# SCH_PIANO_PIC16F88_2024-05-19.net
KiCad netlist of a schematic drawn in EasyEDA
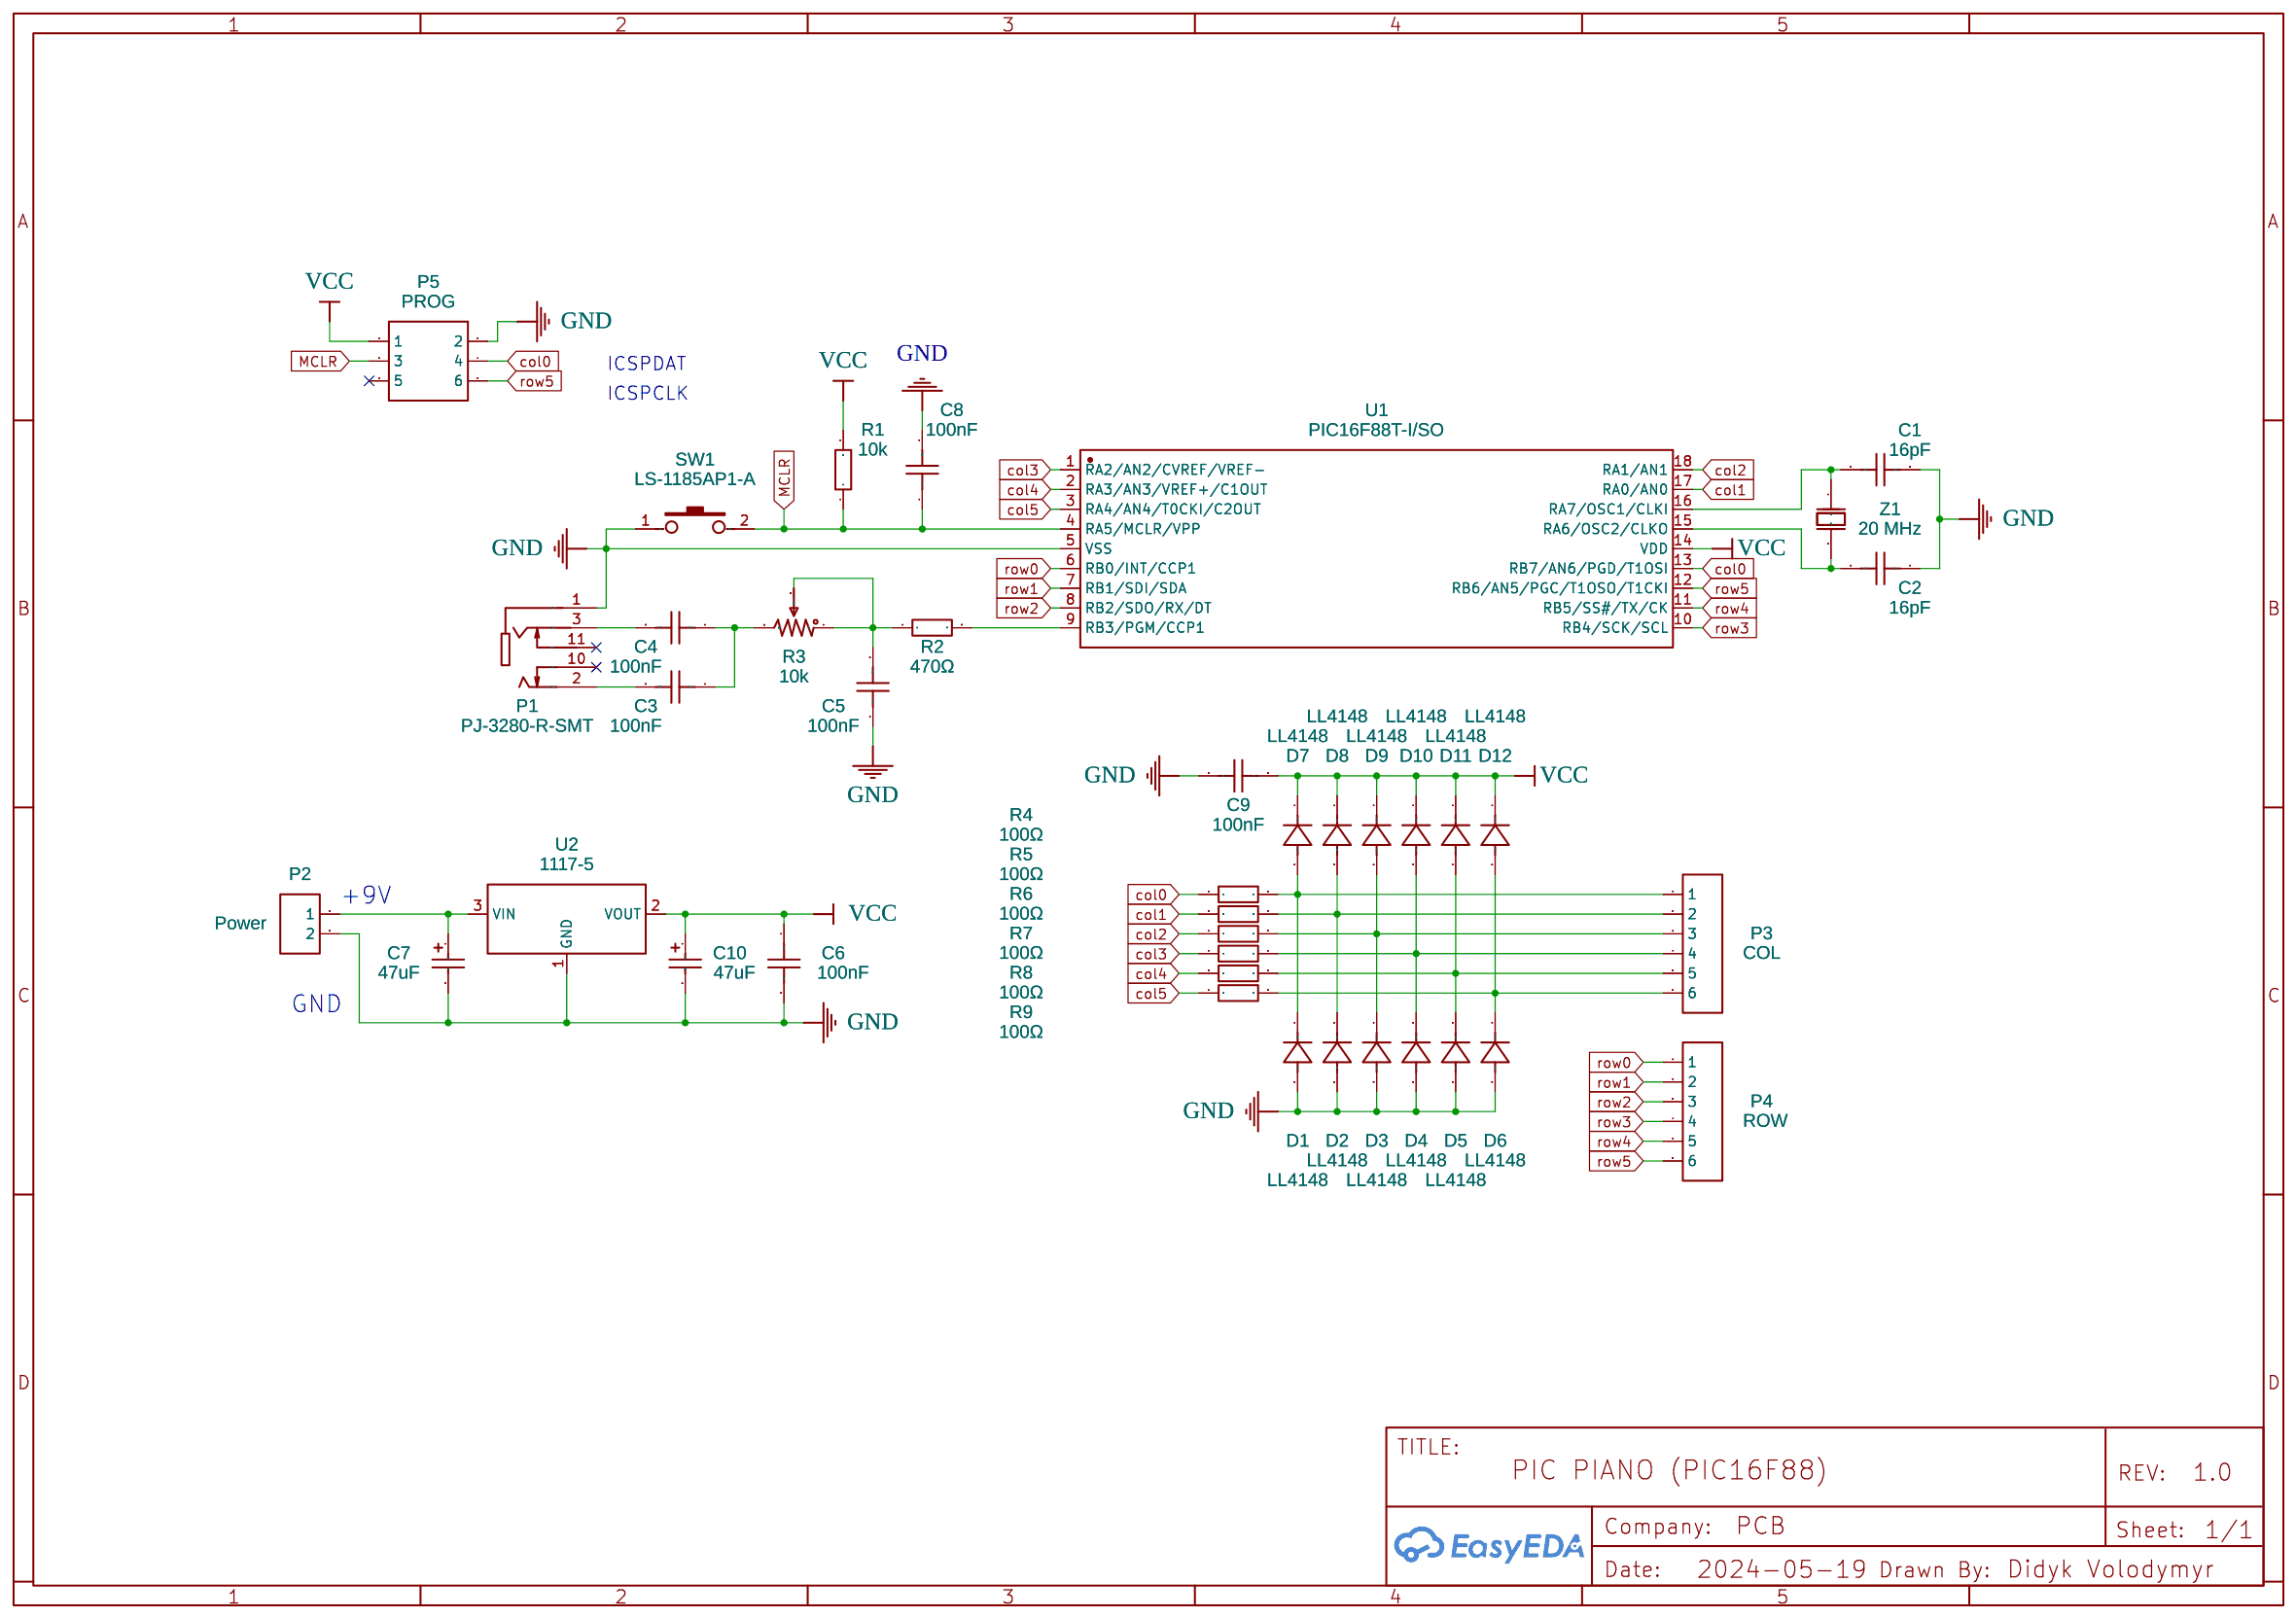
[diagram p0: schematic sheet]

(export (version "E")
  (design (tool "Eeschema 10.0.6"))
  (components
    (comp (ref "C1")
      (value "16pF")
      (fields
        (field (name "Manufacturer Part") "0805N220J500CT-C")
        (field (name "Manufacturer") "Walsin(华新科)")
      )
      (libsource (lib "") (part "0805N220J500CT-C_2"))
    )
    (comp (ref "C2")
      (value "16pF")
      (fields
        (field (name "Manufacturer Part") "0805N220J500CT-C")
        (field (name "Manufacturer") "Walsin(华新科)")
      )
      (libsource (lib "") (part "0805N220J500CT-C"))
    )
    (comp (ref "C3")
      (value "100nF")
      (fields
        (field (name "Manufacturer Part") "0805N220J500CT-C")
        (field (name "Manufacturer") "Walsin(华新科)")
      )
      (libsource (lib "") (part "0805N220J500CT-C"))
    )
    (comp (ref "C4")
      (value "100nF")
      (fields
        (field (name "Manufacturer Part") "0805N220J500CT-C")
        (field (name "Manufacturer") "Walsin(华新科)")
      )
      (libsource (lib "") (part "0805N220J500CT-C"))
    )
    (comp (ref "C5")
      (value "100nF")
      (fields
        (field (name "Manufacturer Part") "0805N220J500CT-C")
        (field (name "Manufacturer") "Walsin(华新科)")
      )
      (libsource (lib "") (part "0805N220J500CT-C_1"))
    )
    (comp (ref "C6")
      (value "100nF")
      (fields
        (field (name "Manufacturer Part") "0805N220J500CT-C")
        (field (name "Manufacturer") "Walsin(华新科)")
      )
      (libsource (lib "") (part "0805N220J500CT-C_3"))
    )
    (comp (ref "C7")
      (value "47uF")
      (fields (field (name "Manufacturer Part") "TAJA106K016RNJ") (field (name "Manufacturer") "Kyocera AVX"))
      (libsource (lib "") (part "TAJA106K016RNJ"))
    )
    (comp (ref "C8")
      (value "100nF")
      (fields
        (field (name "Manufacturer Part") "0805N220J500CT-C")
        (field (name "Manufacturer") "Walsin(华新科)")
      )
      (libsource (lib "") (part "0805N220J500CT-C_1"))
    )
    (comp (ref "C9")
      (value "100nF")
      (fields
        (field (name "Manufacturer Part") "0805N220J500CT-C")
        (field (name "Manufacturer") "Walsin(华新科)")
      )
      (libsource (lib "") (part "0805N220J500CT-C_2"))
    )
    (comp (ref "C10")
      (value "47uF")
      (fields (field (name "Manufacturer Part") "TAJA106K016RNJ") (field (name "Manufacturer") "Kyocera AVX"))
      (libsource (lib "") (part "TAJA106K016RNJ"))
    )
    (comp (ref "D1")
      (value "LL4148")
      (fields (field (name "Manufacturer Part") "LL4148-MS") (field (name "Manufacturer") "MSKSEMI(美森科)"))
      (libsource (lib "") (part "LL4148-MS"))
    )
    (comp (ref "D2")
      (value "LL4148")
      (fields (field (name "Manufacturer Part") "LL4148-MS") (field (name "Manufacturer") "MSKSEMI(美森科)"))
      (libsource (lib "") (part "LL4148-MS"))
    )
    (comp (ref "D3")
      (value "LL4148")
      (fields (field (name "Manufacturer Part") "LL4148-MS") (field (name "Manufacturer") "MSKSEMI(美森科)"))
      (libsource (lib "") (part "LL4148-MS"))
    )
    (comp (ref "D4")
      (value "LL4148")
      (fields (field (name "Manufacturer Part") "LL4148-MS") (field (name "Manufacturer") "MSKSEMI(美森科)"))
      (libsource (lib "") (part "LL4148-MS"))
    )
    (comp (ref "D5")
      (value "LL4148")
      (fields (field (name "Manufacturer Part") "LL4148-MS") (field (name "Manufacturer") "MSKSEMI(美森科)"))
      (libsource (lib "") (part "LL4148-MS"))
    )
    (comp (ref "D6")
      (value "LL4148")
      (fields (field (name "Manufacturer Part") "LL4148-MS") (field (name "Manufacturer") "MSKSEMI(美森科)"))
      (libsource (lib "") (part "LL4148-MS"))
    )
    (comp (ref "D7")
      (value "LL4148")
      (fields (field (name "Manufacturer Part") "LL4148-MS") (field (name "Manufacturer") "MSKSEMI(美森科)"))
      (libsource (lib "") (part "LL4148-MS"))
    )
    (comp (ref "D8")
      (value "LL4148")
      (fields (field (name "Manufacturer Part") "LL4148-MS") (field (name "Manufacturer") "MSKSEMI(美森科)"))
      (libsource (lib "") (part "LL4148-MS"))
    )
    (comp (ref "D9")
      (value "LL4148")
      (fields (field (name "Manufacturer Part") "LL4148-MS") (field (name "Manufacturer") "MSKSEMI(美森科)"))
      (libsource (lib "") (part "LL4148-MS"))
    )
    (comp (ref "D10")
      (value "LL4148")
      (fields (field (name "Manufacturer Part") "LL4148-MS") (field (name "Manufacturer") "MSKSEMI(美森科)"))
      (libsource (lib "") (part "LL4148-MS"))
    )
    (comp (ref "D11")
      (value "LL4148")
      (fields (field (name "Manufacturer Part") "LL4148-MS") (field (name "Manufacturer") "MSKSEMI(美森科)"))
      (libsource (lib "") (part "LL4148-MS"))
    )
    (comp (ref "D12")
      (value "LL4148")
      (fields (field (name "Manufacturer Part") "LL4148-MS") (field (name "Manufacturer") "MSKSEMI(美森科)"))
      (libsource (lib "") (part "LL4148-MS"))
    )
    (comp (ref "P1")
      (value "PJ-3280-R-SMT")
      (fields (field (name "Manufacturer") "XKB Connectivity(中国星坤)"))
      (libsource (lib "") (part "PJ-3280-R-SMT"))
    )
    (comp (ref "P2") (value "Power") (libsource (lib "") (part "HDR-M-2.54_1x2")))
    (comp (ref "P3") (value "COL") (libsource (lib "") (part "HDR-M-2.54_1x6")))
    (comp (ref "P4") (value "ROW") (libsource (lib "") (part "HDR-M-2.54_1x6")))
    (comp (ref "P5") (value "PROG") (libsource (lib "") (part "HDR-F-2.54_2x3")))
    (comp (ref "R1")
      (value "10k")
      (fields (field (name "Manufacturer Part") "AF0805JR-07100RL") (field (name "Manufacturer") "YAGEO(国巨)"))
      (libsource (lib "") (part "AF0805JR-07100RL_1"))
    )
    (comp (ref "R2")
      (value "470Ω")
      (fields (field (name "Manufacturer Part") "AF0805JR-07100RL") (field (name "Manufacturer") "YAGEO(国巨)"))
      (libsource (lib "") (part "AF0805JR-07100RL"))
    )
    (comp (ref "R3")
      (value "10k")
      (fields (field (name "Manufacturer Part") "3362P-1-504") (field (name "Manufacturer") "BOCHEN(博晨)"))
      (libsource (lib "") (part "3362P-1-504"))
    )
    (comp (ref "R4")
      (value "100Ω")
      (fields (field (name "Manufacturer Part") "AF0805JR-07100RL") (field (name "Manufacturer") "YAGEO(国巨)"))
      (libsource (lib "") (part "AF0805JR-07100RL"))
    )
    (comp (ref "R5")
      (value "100Ω")
      (fields (field (name "Manufacturer Part") "AF0805JR-07100RL") (field (name "Manufacturer") "YAGEO(国巨)"))
      (libsource (lib "") (part "AF0805JR-07100RL"))
    )
    (comp (ref "R6")
      (value "100Ω")
      (fields (field (name "Manufacturer Part") "AF0805JR-07100RL") (field (name "Manufacturer") "YAGEO(国巨)"))
      (libsource (lib "") (part "AF0805JR-07100RL"))
    )
    (comp (ref "R7")
      (value "100Ω")
      (fields (field (name "Manufacturer Part") "AF0805JR-07100RL") (field (name "Manufacturer") "YAGEO(国巨)"))
      (libsource (lib "") (part "AF0805JR-07100RL"))
    )
    (comp (ref "R8")
      (value "100Ω")
      (fields (field (name "Manufacturer Part") "AF0805JR-07100RL") (field (name "Manufacturer") "YAGEO(国巨)"))
      (libsource (lib "") (part "AF0805JR-07100RL"))
    )
    (comp (ref "R9")
      (value "100Ω")
      (fields (field (name "Manufacturer Part") "AF0805JR-07100RL") (field (name "Manufacturer") "YAGEO(国巨)"))
      (libsource (lib "") (part "AF0805JR-07100RL"))
    )
    (comp (ref "SW1") (value "LS-1185AP1-A") (libsource (lib "") (part "LS-1185AP1-A")))
    (comp (ref "U1")
      (value "PIC16F88T-I/SO")
      (fields (field (name "Manufacturer") "MICROCHIP(美国微芯)"))
      (libsource (lib "") (part "PIC16F88T-I/SO"))
    )
    (comp (ref "U2")
      (value "1117-5")
      (fields (field (name "Manufacturer") "IDCHIP(英锐芯)"))
      (libsource (lib "") (part "1117-5"))
    )
    (comp (ref "Z1")
      (value "20 MHz")
      (fields (field (name "Manufacturer Part") "SIP-2HC-49S"))
      (libsource (lib "") (part "SIP-2HC-49S"))
    )
  )
  (nets
    (net (code "1") (name "GND") (class "Default")
      (node (ref "C1") (pin "2") (pinfunction "2_2") (pintype "unspecified"))
      (node (ref "C10") (pin "2") (pinfunction "2_2") (pintype "input"))
      (node (ref "C2") (pin "1") (pinfunction "1_1") (pintype "unspecified"))
      (node (ref "C5") (pin "1") (pinfunction "1_1") (pintype "unspecified"))
      (node (ref "C6") (pin "2") (pinfunction "2_2") (pintype "unspecified"))
      (node (ref "C7") (pin "2") (pinfunction "2_2") (pintype "input"))
      (node (ref "C8") (pin "2") (pinfunction "2_2") (pintype "unspecified"))
      (node (ref "C9") (pin "1") (pinfunction "1_1") (pintype "unspecified"))
      (node (ref "D1") (pin "2") (pinfunction "A_2") (pintype "unspecified"))
      (node (ref "D2") (pin "2") (pinfunction "A_2") (pintype "unspecified"))
      (node (ref "D3") (pin "2") (pinfunction "A_2") (pintype "unspecified"))
      (node (ref "D4") (pin "2") (pinfunction "A_2") (pintype "unspecified"))
      (node (ref "D5") (pin "2") (pinfunction "A_2") (pintype "unspecified"))
      (node (ref "D6") (pin "2") (pinfunction "A_2") (pintype "unspecified"))
      (node (ref "P1") (pin "1") (pinfunction "1_1") (pintype "unspecified"))
      (node (ref "P2") (pin "2") (pinfunction "2_2") (pintype "unspecified"))
      (node (ref "P5") (pin "2") (pinfunction "2_2") (pintype "input"))
      (node (ref "SW1") (pin "1") (pinfunction "1_1") (pintype "input"))
      (node (ref "U1") (pin "5") (pinfunction "VSS_5") (pintype "unspecified"))
      (node (ref "U2") (pin "1") (pinfunction "GND_1") (pintype "unspecified"))
    )
    (net (code "2") (name "MCLR") (class "Default")
      (node (ref "C8") (pin "1") (pinfunction "1_1") (pintype "unspecified"))
      (node (ref "P5") (pin "3") (pinfunction "3_3") (pintype "input"))
      (node (ref "R1") (pin "1") (pinfunction "1_1") (pintype "unspecified"))
      (node (ref "SW1") (pin "2") (pinfunction "2_2") (pintype "input"))
      (node (ref "U1") (pin "4") (pinfunction "RA5/MCLR/VPP_4") (pintype "unspecified"))
    )
    (net (code "3") (name "Net-(C3-Pad1)") (class "Default")
      (node (ref "C3") (pin "1") (pinfunction "1_1") (pintype "unspecified"))
      (node (ref "C4") (pin "1") (pinfunction "1_1") (pintype "unspecified"))
      (node (ref "R3") (pin "3") (pinfunction "3_3") (pintype "unspecified"))
    )
    (net (code "4") (name "Net-(C4-Pad2)") (class "Default")
      (node (ref "C4") (pin "2") (pinfunction "2_2") (pintype "unspecified"))
      (node (ref "P1") (pin "3") (pinfunction "3_3") (pintype "unspecified"))
    )
    (net (code "5") (name "Net-(C5-Pad2)") (class "Default")
      (node (ref "C5") (pin "2") (pinfunction "2_2") (pintype "unspecified"))
      (node (ref "R2") (pin "1") (pinfunction "1_1") (pintype "unspecified"))
      (node (ref "R3") (pin "1") (pinfunction "1_1") (pintype "unspecified"))
      (node (ref "R3") (pin "2") (pinfunction "2_2") (pintype "unspecified"))
    )
    (net (code "6") (name "Net-(D1-K)") (class "Default")
      (node (ref "D1") (pin "1") (pinfunction "K_1") (pintype "unspecified"))
      (node (ref "D7") (pin "2") (pinfunction "A_2") (pintype "unspecified"))
      (node (ref "P3") (pin "1") (pinfunction "1_1") (pintype "input"))
      (node (ref "R4") (pin "2") (pinfunction "2_2") (pintype "unspecified"))
    )
    (net (code "7") (name "Net-(D2-K)") (class "Default")
      (node (ref "D2") (pin "1") (pinfunction "K_1") (pintype "unspecified"))
      (node (ref "D8") (pin "2") (pinfunction "A_2") (pintype "unspecified"))
      (node (ref "P3") (pin "2") (pinfunction "2_2") (pintype "input"))
      (node (ref "R5") (pin "2") (pinfunction "2_2") (pintype "unspecified"))
    )
    (net (code "8") (name "Net-(D3-K)") (class "Default")
      (node (ref "D3") (pin "1") (pinfunction "K_1") (pintype "unspecified"))
      (node (ref "D9") (pin "2") (pinfunction "A_2") (pintype "unspecified"))
      (node (ref "P3") (pin "3") (pinfunction "3_3") (pintype "input"))
      (node (ref "R6") (pin "2") (pinfunction "2_2") (pintype "unspecified"))
    )
    (net (code "9") (name "Net-(D10-A)") (class "Default")
      (node (ref "D10") (pin "2") (pinfunction "A_2") (pintype "unspecified"))
      (node (ref "D4") (pin "1") (pinfunction "K_1") (pintype "unspecified"))
      (node (ref "P3") (pin "4") (pinfunction "4_4") (pintype "input"))
      (node (ref "R7") (pin "2") (pinfunction "2_2") (pintype "unspecified"))
    )
    (net (code "10") (name "Net-(D11-A)") (class "Default")
      (node (ref "D11") (pin "2") (pinfunction "A_2") (pintype "unspecified"))
      (node (ref "D5") (pin "1") (pinfunction "K_1") (pintype "unspecified"))
      (node (ref "P3") (pin "5") (pinfunction "5_5") (pintype "input"))
      (node (ref "R8") (pin "2") (pinfunction "2_2") (pintype "unspecified"))
    )
    (net (code "11") (name "Net-(D12-A)") (class "Default")
      (node (ref "D12") (pin "2") (pinfunction "A_2") (pintype "unspecified"))
      (node (ref "D6") (pin "1") (pinfunction "K_1") (pintype "unspecified"))
      (node (ref "P3") (pin "6") (pinfunction "6_6") (pintype "input"))
      (node (ref "R9") (pin "2") (pinfunction "2_2") (pintype "unspecified"))
    )
    (net (code "12") (name "Net-(P1-5)") (class "Default")
      (node (ref "C3") (pin "2") (pinfunction "2_2") (pintype "unspecified"))
      (node (ref "P1") (pin "2") (pinfunction "5_2") (pintype "unspecified"))
    )
    (net (code "13") (name "Net-(U1-RA6{slash}OSC2{slash}CLKO)") (class "Default")
      (node (ref "C2") (pin "2") (pinfunction "2_2") (pintype "unspecified"))
      (node (ref "U1") (pin "15") (pinfunction "RA6/OSC2/CLKO_15") (pintype "unspecified"))
      (node (ref "Z1") (pin "2") (pinfunction "OSC2_2") (pintype "input"))
    )
    (net (code "14") (name "Net-(U1-RA7{slash}OSC1{slash}CLKI)") (class "Default")
      (node (ref "C1") (pin "1") (pinfunction "1_1") (pintype "unspecified"))
      (node (ref "U1") (pin "16") (pinfunction "RA7/OSC1/CLKI_16") (pintype "unspecified"))
      (node (ref "Z1") (pin "1") (pinfunction "OSC1_1") (pintype "input"))
    )
    (net (code "15") (name "Net-(U1-RB3{slash}PGM{slash}CCP1)") (class "Default")
      (node (ref "R2") (pin "2") (pinfunction "2_2") (pintype "unspecified"))
      (node (ref "U1") (pin "9") (pinfunction "RB3/PGM/CCP1_9") (pintype "unspecified"))
    )
    (net (code "16") (name "Net-(U2-VIN)") (class "Default")
      (node (ref "C7") (pin "1") (pinfunction "1_1") (pintype "input"))
      (node (ref "P2") (pin "1") (pinfunction "1_1") (pintype "unspecified"))
      (node (ref "U2") (pin "3") (pinfunction "VIN_3") (pintype "unspecified"))
    )
    (net (code "17") (name "VCC") (class "Default")
      (node (ref "C10") (pin "1") (pinfunction "1_1") (pintype "input"))
      (node (ref "C6") (pin "1") (pinfunction "1_1") (pintype "unspecified"))
      (node (ref "C9") (pin "2") (pinfunction "2_2") (pintype "unspecified"))
      (node (ref "D10") (pin "1") (pinfunction "K_1") (pintype "unspecified"))
      (node (ref "D11") (pin "1") (pinfunction "K_1") (pintype "unspecified"))
      (node (ref "D12") (pin "1") (pinfunction "K_1") (pintype "unspecified"))
      (node (ref "D7") (pin "1") (pinfunction "K_1") (pintype "unspecified"))
      (node (ref "D8") (pin "1") (pinfunction "K_1") (pintype "unspecified"))
      (node (ref "D9") (pin "1") (pinfunction "K_1") (pintype "unspecified"))
      (node (ref "P5") (pin "1") (pinfunction "1_1") (pintype "input"))
      (node (ref "R1") (pin "2") (pinfunction "2_2") (pintype "unspecified"))
      (node (ref "U1") (pin "14") (pinfunction "VDD_14") (pintype "unspecified"))
      (node (ref "U2") (pin "2") (pinfunction "VOUT_2") (pintype "unspecified"))
    )
    (net (code "18") (name "col0") (class "Default")
      (node (ref "P5") (pin "4") (pinfunction "4_4") (pintype "input"))
      (node (ref "R4") (pin "1") (pinfunction "1_1") (pintype "unspecified"))
      (node (ref "U1") (pin "13") (pinfunction "RB7/AN6/PGD/T1OSI_13") (pintype "unspecified"))
    )
    (net (code "19") (name "col1") (class "Default")
      (node (ref "R5") (pin "1") (pinfunction "1_1") (pintype "unspecified"))
      (node (ref "U1") (pin "17") (pinfunction "RA0/AN0_17") (pintype "unspecified"))
    )
    (net (code "20") (name "col2") (class "Default")
      (node (ref "R6") (pin "1") (pinfunction "1_1") (pintype "unspecified"))
      (node (ref "U1") (pin "18") (pinfunction "RA1/AN1_18") (pintype "unspecified"))
    )
    (net (code "21") (name "col3") (class "Default")
      (node (ref "R7") (pin "1") (pinfunction "1_1") (pintype "unspecified"))
      (node (ref "U1") (pin "1") (pinfunction "RA2/AN2/CVREF/VREF-_1") (pintype "unspecified"))
    )
    (net (code "22") (name "col4") (class "Default")
      (node (ref "R8") (pin "1") (pinfunction "1_1") (pintype "unspecified"))
      (node (ref "U1") (pin "2") (pinfunction "RA3/AN3/VREF+/C1OUT_2") (pintype "unspecified"))
    )
    (net (code "23") (name "col5") (class "Default")
      (node (ref "R9") (pin "1") (pinfunction "1_1") (pintype "unspecified"))
      (node (ref "U1") (pin "3") (pinfunction "RA4/AN4/T0CKI/C2OUT_3") (pintype "unspecified"))
    )
    (net (code "24") (name "row0") (class "Default")
      (node (ref "P4") (pin "1") (pinfunction "1_1") (pintype "input"))
      (node (ref "U1") (pin "6") (pinfunction "RB0/INT/CCP1_6") (pintype "unspecified"))
    )
    (net (code "25") (name "row1") (class "Default")
      (node (ref "P4") (pin "2") (pinfunction "2_2") (pintype "input"))
      (node (ref "U1") (pin "7") (pinfunction "RB1/SDI/SDA_7") (pintype "unspecified"))
    )
    (net (code "26") (name "row2") (class "Default")
      (node (ref "P4") (pin "3") (pinfunction "3_3") (pintype "input"))
      (node (ref "U1") (pin "8") (pinfunction "RB2/SDO/RX/DT_8") (pintype "unspecified"))
    )
    (net (code "27") (name "row3") (class "Default")
      (node (ref "P4") (pin "4") (pinfunction "4_4") (pintype "input"))
      (node (ref "U1") (pin "10") (pinfunction "RB4/SCK/SCL_10") (pintype "unspecified"))
    )
    (net (code "28") (name "row4") (class "Default")
      (node (ref "P4") (pin "5") (pinfunction "5_5") (pintype "input"))
      (node (ref "U1") (pin "11") (pinfunction "RB5/SS#/TX/CK_11") (pintype "unspecified"))
    )
    (net (code "29") (name "row5") (class "Default")
      (node (ref "P4") (pin "6") (pinfunction "6_6") (pintype "input"))
      (node (ref "P5") (pin "6") (pinfunction "6_6") (pintype "input"))
      (node (ref "U1") (pin "12") (pinfunction "RB6/AN5/PGC/T1OSO/T1CKI_12") (pintype "unspecified"))
    )
    (net (code "30") (name "unconnected-(P1-Pad10)") (class "Default")
      (node (ref "P1") (pin "10") (pinfunction "10_10") (pintype "unspecified+no_connect"))
    )
    (net (code "31") (name "unconnected-(P1-Pad11)") (class "Default")
      (node (ref "P1") (pin "11") (pinfunction "11_11") (pintype "unspecified+no_connect"))
    )
    (net (code "32") (name "unconnected-(P5-Pad5)") (class "Default")
      (node (ref "P5") (pin "5") (pinfunction "5_5") (pintype "input+no_connect"))
    )
  )
)
